# Power.net
KiCad netlist of a schematic drawn in Altium Designer
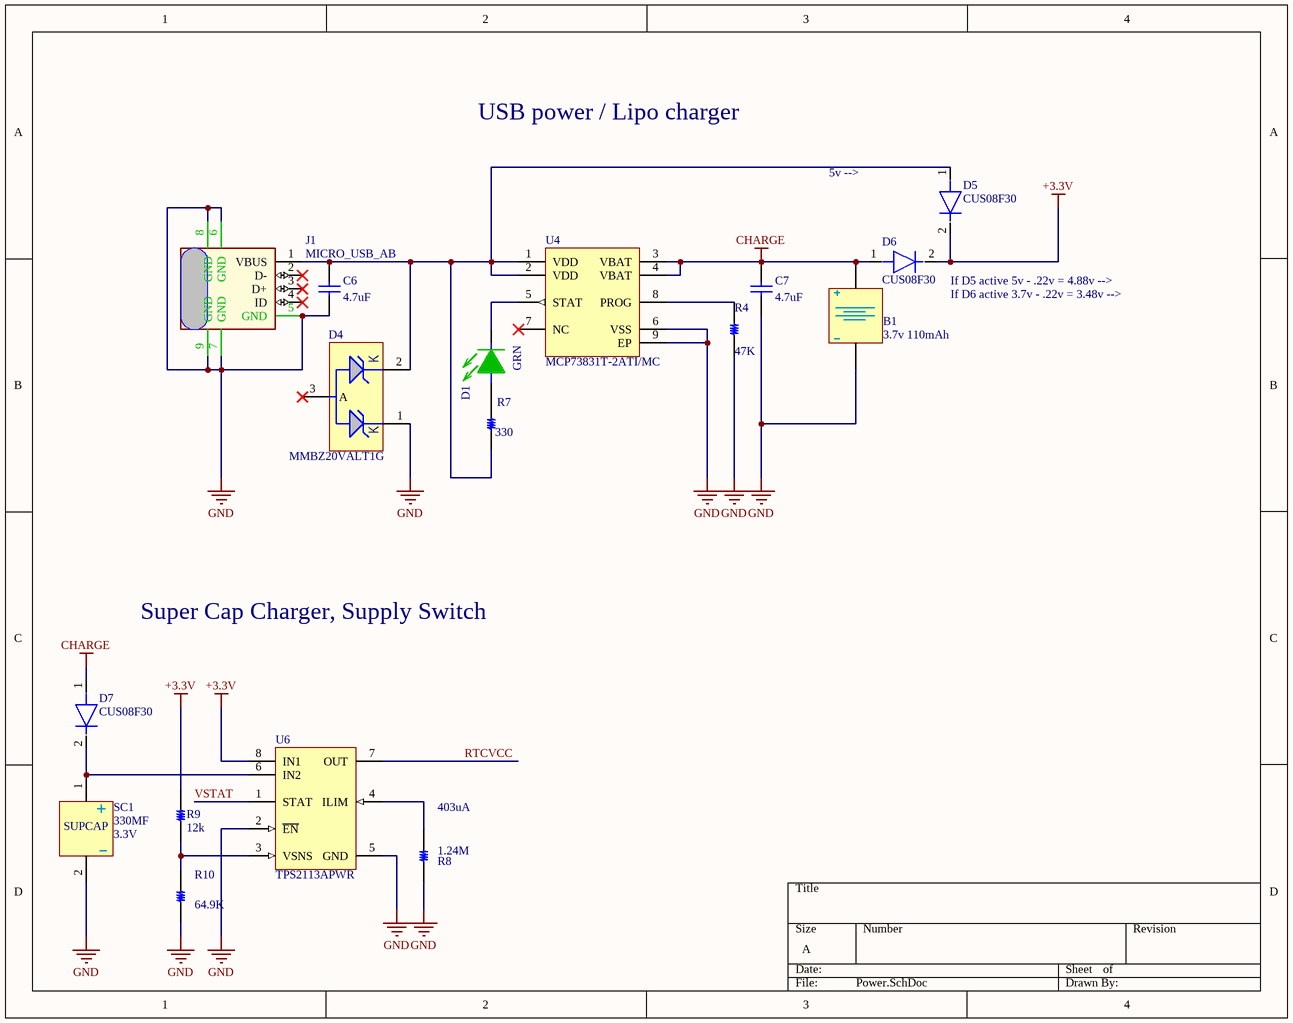
[diagram p0: Power.SchDoc]

(export (version "E")
  (design (tool "Eeschema 10.0.6"))
  (components
    (comp (ref "B1")
      (value "3.7v 110mAh")
      (footprint "BATTERY:LIPO_110mAh")
      (description "400mAh_Lipo_battery")
      (fields (field (name "Comment") "LIPO_400mAh_Sparkfun"))
      (libsource (lib "BATTERY") (part "LIPO_400mAh_Sparkfun"))
    )
    (comp (ref "C6")
      (value "4.7uF")
      (footprint "DISCRETE:C1608L")
      (description "CAP CER 4.7UF 6.3V 20% X5R 0603")
      (fields (field (name "PART NUMBER") "C1608X5R0J475M/0.80") (field (name "TOLERANCE") "20%"))
      (libsource (lib "DISCRETE_CAP") (part "C475-0603-X5R-20%"))
    )
    (comp (ref "C7")
      (value "4.7uF")
      (footprint "DISCRETE:C1608L")
      (description "CAP CER 4.7UF 6.3V 20% X5R 0603")
      (fields (field (name "PART NUMBER") "C1608X5R0J475M/0.80") (field (name "TOLERANCE") "20%"))
      (libsource (lib "DISCRETE_CAP") (part "C475-0603-X5R-20%"))
    )
    (comp (ref "D1")
      (value "GRN")
      (footprint "EMECH_OPTO:LEDCP2015X08L")
      (description "LED THIN 565NM GRN DIFF 0805 SMD")
      (fields (field (name "PART NUMBER") "SML-LXT0805GW-TR") (field (name "VOLTAGE") "1.8V"))
      (libsource (lib "EMECH_OPTO") (part "LED-GRN-0805-LUMEX-SML-LXT0805SGW"))
    )
    (comp (ref "D4")
      (value "TVS_MMBZ20VALT1G_OnSemi")
      (footprint "DISCRETE:SOT23_95P237x111-3N")
      (description "TVS DIODE 17VWM 28VC SOT23")
      (fields (field (name "MANUFACTURER PART NUMBER 1") "MMBZ20VALT1G"))
      (libsource (lib "DISCRETE_DIODE") (part "TVS_MMBZ20VALT1G_OnSemi"))
    )
    (comp (ref "D5")
      (value "CUS08F30")
      (footprint "DISCRETE:DIODE-USC")
      (description "DIODE SCHOTTKY 30V 800MA USC")
      (libsource (lib "DISCRETE_DIODE") (part "DIODE-CUS08F30-30v-800MA-USC-Toshiba"))
    )
    (comp (ref "D6")
      (value "CUS08F30")
      (footprint "DISCRETE:DIODE-USC")
      (description "DIODE SCHOTTKY 30V 800MA USC")
      (libsource (lib "DISCRETE_DIODE") (part "DIODE-CUS08F30-30v-800MA-USC-Toshiba"))
    )
    (comp (ref "D7")
      (value "CUS08F30")
      (footprint "DISCRETE:DIODE-USC")
      (description "DIODE SCHOTTKY 30V 800MA USC")
      (libsource (lib "DISCRETE_DIODE") (part "DIODE-CUS08F30-30v-800MA-USC-Toshiba"))
    )
    (comp (ref "J1")
      (value "MICRO_USB_AB")
      (footprint "CONN USB_MIcro")
      (fields (field (name "MANUFACTURER") "HIROSE") (field (name "PART NUMBER") "ZX62-AB-5P"))
      (libsource (lib "EMECH_CONNECTOR") (part "CONN_MICRO_USB_AB"))
    )
    (comp (ref "R4")
      (value "47K")
      (footprint "DISCRETE:C1005L")
      (description "DEPRECATED - RES 47K OHM 1/10W 5% 0402 SMD")
      (fields (field (name "PART NUMBER") "CR0402-16W-473JT") (field (name "MANUFACTURER") "Venkel LTD"))
      (libsource (lib "DISCRETE_RESISTOR") (part "R473-0402-5%"))
    )
    (comp (ref "R7")
      (value "330")
      (footprint "DISCRETE:C1005L")
      (fields (field (name "Comment") "R331-0402-5%"))
      (libsource (lib "DISCRETE_RESISTOR") (part "R331-0402-5%"))
    )
    (comp (ref "R8")
      (value "1.24M")
      (footprint "DISCRETE:C1608N")
      (description "RES SMD 4.7M OHM 5% 1/10W 0603")
      (libsource (lib "DISCRETE_RESISTOR") (part "R4.7M-0603-5%-Yageo"))
    )
    (comp (ref "R9")
      (value "12k")
      (footprint "DISCRETE:C1608N")
      (description "RES SMD 12K OHM 5% 1/10W 0603")
      (fields (field (name "Comment") "R123_0603_5%_Panasonic"))
      (libsource (lib "DISCRETE_RESISTOR") (part "R123_0603_5%_Panasonic"))
    )
    (comp (ref "R10")
      (value "64.9K")
      (footprint "DISCRETE:C1608L")
      (description "RES SMD 64.9 OHM 1% 1/10W 0603")
      (fields (field (name "Comment") "R643R9-0603-1%_Yageo"))
      (libsource (lib "DISCRETE_RESISTOR") (part "R643R9-0603-1%_Yageo"))
    )
    (comp (ref "SC1")
      (value "330MF")
      (footprint "Super_Caps:SUPCAP_330MF")
      (description "CAP 330MF -20% +80% 3.3V SMD")
      (fields (field (name "Comment") "SUPCAP_330MF_SMD"))
      (libsource (lib "Super_Caps") (part "SUPCAP_330MF_SMD"))
    )
    (comp (ref "U4")
      (value "MCP73831T-2ATI/MC")
      (footprint "DFN-MC8")
      (fields (field (name "MANUFACTURER") "Microchip"))
      (libsource (lib "Microchip Power Management Battery Management") (part "MCP73831T-2ATI/MC"))
    )
    (comp (ref "U6")
      (value "TPS2113APWR")
      (footprint "PW8_N")
      (fields (field (name "MANUFACTURER") "Texas Instruments"))
      (libsource (lib "TI Power Management Power Multiplexer (MUX)") (part "TPS2113APWR"))
    )
  )
  (nets
    (net (code "1") (name "+3.3V") (class "Default")
      (node (ref "D5") (pin "2") (pintype "passive"))
      (node (ref "D6") (pin "2") (pintype "passive"))
      (node (ref "R9") (pin "2") (pinfunction "2_2") (pintype "passive"))
      (node (ref "U6") (pin "8") (pinfunction "IN1_8") (pintype "power_in"))
    )
    (net (code "2") (name "/RTCVCC") (class "Default")
      (node (ref "U6") (pin "7") (pinfunction "OUT_7") (pintype "power_in"))
    )
    (net (code "3") (name "/VSTAT") (class "Default")
      (node (ref "U6") (pin "1") (pinfunction "STAT_1") (pintype "tri_state"))
    )
    (net (code "4") (name "CHARGE") (class "Default")
      (node (ref "B1") (pin "1") (pinfunction "1_1") (pintype "passive"))
      (node (ref "C7") (pin "2") (pinfunction "2_2") (pintype "passive"))
      (node (ref "D6") (pin "1") (pintype "passive"))
      (node (ref "D7") (pin "1") (pintype "passive"))
      (node (ref "U4") (pin "3") (pinfunction "VBAT_3") (pintype "power_in"))
      (node (ref "U4") (pin "4") (pinfunction "VBAT_4") (pintype "power_in"))
    )
    (net (code "5") (name "GND") (class "Default")
      (node (ref "B1") (pin "2") (pinfunction "2_2") (pintype "passive"))
      (node (ref "C6") (pin "1") (pinfunction "1_1") (pintype "passive"))
      (node (ref "C7") (pin "1") (pinfunction "1_1") (pintype "passive"))
      (node (ref "D4") (pin "1") (pinfunction "K_1") (pintype "passive"))
      (node (ref "J1") (pin "5") (pinfunction "GND_5") (pintype "power_in"))
      (node (ref "J1") (pin "6") (pinfunction "GND_6") (pintype "power_in"))
      (node (ref "J1") (pin "7") (pinfunction "GND_7") (pintype "power_in"))
      (node (ref "J1") (pin "8") (pinfunction "GND_8") (pintype "power_in"))
      (node (ref "J1") (pin "9") (pinfunction "GND_9") (pintype "power_in"))
      (node (ref "R10") (pin "1") (pinfunction "1_1") (pintype "passive"))
      (node (ref "R4") (pin "1") (pinfunction "1_1") (pintype "passive"))
      (node (ref "R8") (pin "1") (pinfunction "1_1") (pintype "passive"))
      (node (ref "SC1") (pin "2") (pinfunction "2_2") (pintype "passive"))
      (node (ref "U4") (pin "6") (pinfunction "VSS_6") (pintype "power_in"))
      (node (ref "U4") (pin "9") (pinfunction "EP_9") (pintype "power_in"))
      (node (ref "U6") (pin "2") (pinfunction "~{EN}_2") (pintype "input"))
      (node (ref "U6") (pin "5") (pinfunction "GND_5") (pintype "power_in"))
    )
    (net (code "6") (name "Net-(D1-Pad1)") (class "Default")
      (node (ref "D1") (pin "1") (pintype "passive"))
      (node (ref "R7") (pin "2") (pinfunction "2_2") (pintype "passive"))
    )
    (net (code "7") (name "Net-(J1-VBUS)") (class "Default")
      (node (ref "C6") (pin "2") (pinfunction "2_2") (pintype "passive"))
      (node (ref "D4") (pin "2") (pinfunction "K_2") (pintype "passive"))
      (node (ref "D5") (pin "1") (pintype "passive"))
      (node (ref "J1") (pin "1") (pinfunction "VBUS_1") (pintype "power_in"))
      (node (ref "R7") (pin "1") (pinfunction "1_1") (pintype "passive"))
      (node (ref "U4") (pin "1") (pinfunction "VDD_1") (pintype "power_in"))
      (node (ref "U4") (pin "2") (pinfunction "VDD_2") (pintype "power_in"))
    )
    (net (code "8") (name "Net-(U4-PROG)") (class "Default")
      (node (ref "R4") (pin "2") (pinfunction "2_2") (pintype "passive"))
      (node (ref "U4") (pin "8") (pinfunction "PROG_8") (pintype "passive"))
    )
    (net (code "9") (name "Net-(U4-STAT)") (class "Default")
      (node (ref "D1") (pin "2") (pintype "passive"))
      (node (ref "U4") (pin "5") (pinfunction "STAT_5") (pintype "output"))
    )
    (net (code "10") (name "Net-(U6-ILIM)") (class "Default")
      (node (ref "R8") (pin "2") (pinfunction "2_2") (pintype "passive"))
      (node (ref "U6") (pin "4") (pinfunction "ILIM_4") (pintype "input"))
    )
    (net (code "11") (name "Net-(U6-IN2)") (class "Default")
      (node (ref "D7") (pin "2") (pintype "passive"))
      (node (ref "SC1") (pin "1") (pinfunction "1_1") (pintype "passive"))
      (node (ref "U6") (pin "6") (pinfunction "IN2_6") (pintype "power_in"))
    )
    (net (code "12") (name "Net-(U6-VSNS)") (class "Default")
      (node (ref "R10") (pin "2") (pinfunction "2_2") (pintype "passive"))
      (node (ref "R9") (pin "1") (pinfunction "1_1") (pintype "passive"))
      (node (ref "U6") (pin "3") (pinfunction "VSNS_3") (pintype "input"))
    )
    (net (code "13") (name "unconnected-(D4-A-Pad3)") (class "Default")
      (node (ref "D4") (pin "3") (pinfunction "A_3") (pintype "passive+no_connect"))
    )
    (net (code "14") (name "unconnected-(J1-D+-Pad3)") (class "Default")
      (node (ref "J1") (pin "3") (pinfunction "D+_3") (pintype "bidirectional+no_connect"))
    )
    (net (code "15") (name "unconnected-(J1-D--Pad2)") (class "Default")
      (node (ref "J1") (pin "2") (pinfunction "D-_2") (pintype "bidirectional+no_connect"))
    )
    (net (code "16") (name "unconnected-(J1-ID-Pad4)") (class "Default")
      (node (ref "J1") (pin "4") (pinfunction "ID_4") (pintype "bidirectional+no_connect"))
    )
    (net (code "17") (name "unconnected-(U4-NC-Pad7)") (class "Default")
      (node (ref "U4") (pin "7") (pinfunction "NC_7") (pintype "passive+no_connect"))
    )
  )
)
